# germanium_diode_radio.net
KiCad netlist of a schematic drawn in EAGLE
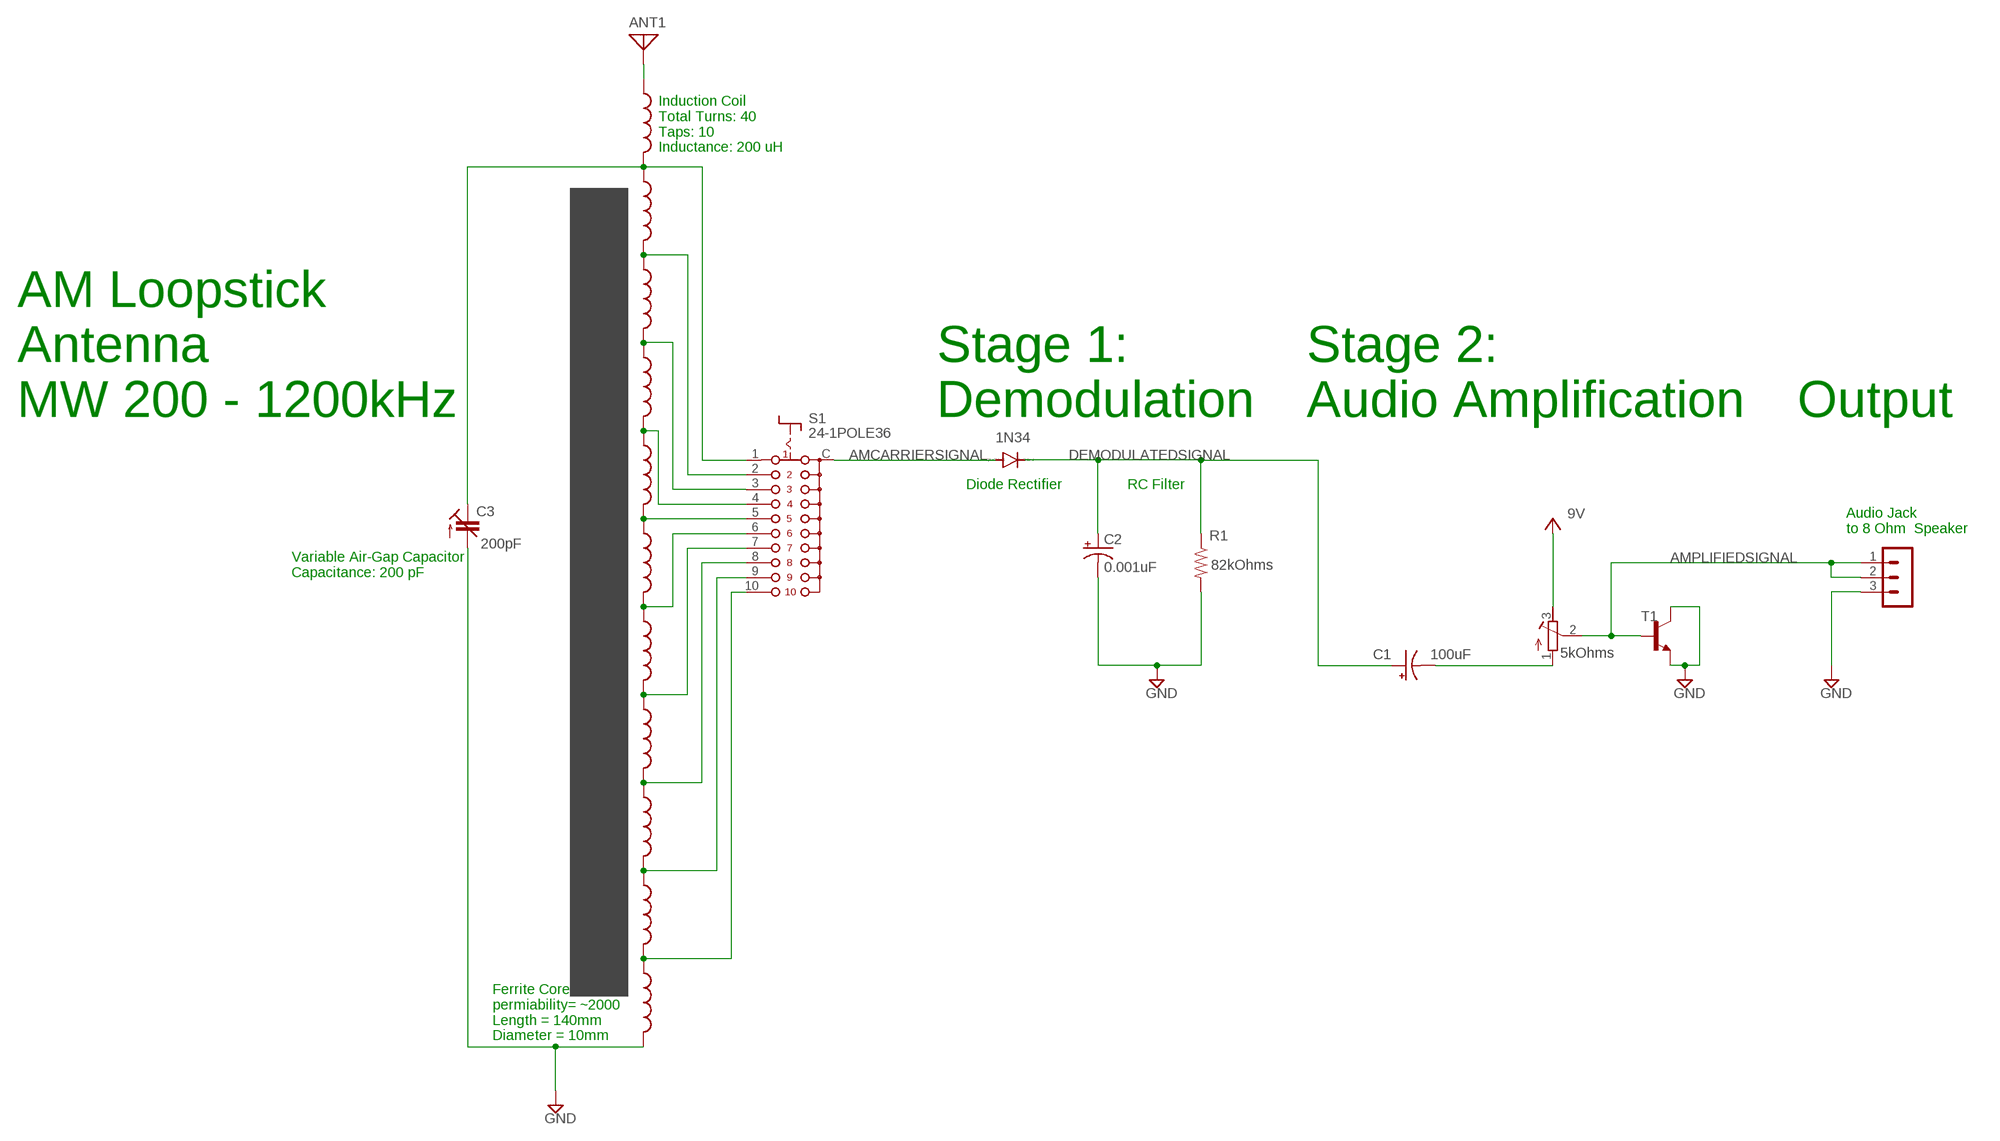
[diagram p0: schematic, sheet 1]

(export (version "E")
  (design (tool "Eeschema 10.0.6"))
  (components
    (comp (ref "1N34")
      (value "AA112")
      (footprint "eagle-import:DO07")
      (libsource (lib "eagle-import") (part "AA112"))
    )
    (comp (ref "ANT1")
      (value "ANTENNA")
      (footprint "eagle-import:PAD-01")
      (libsource (lib "eagle-import") (part "ANTENNA"))
    )
    (comp (ref "C1")
      (value "100uF")
      (footprint "eagle-import:E1,8-4")
      (libsource (lib "eagle-import") (part "CPOL-USE1.8-4"))
    )
    (comp (ref "C2")
      (value "0.001uF")
      (footprint "eagle-import:E1,8-4")
      (libsource (lib "eagle-import") (part "CPOL-USE1.8-4"))
    )
    (comp (ref "C3")
      (value "200pF")
      (footprint "eagle-import:CTRIMTZ03")
      (libsource (lib "eagle-import") (part "C-TRIMMTZ03"))
    )
    (comp (ref "L1")
      (value "L-US0204/7")
      (footprint "eagle-import:0204_7")
      (libsource (lib "eagle-import") (part "L-US0204/7"))
    )
    (comp (ref "L2")
      (value "L-US0204/7")
      (footprint "eagle-import:0204_7")
      (libsource (lib "eagle-import") (part "L-US0204/7"))
    )
    (comp (ref "L3")
      (value "L-US0204/7")
      (footprint "eagle-import:0204_7")
      (libsource (lib "eagle-import") (part "L-US0204/7"))
    )
    (comp (ref "L4")
      (value "L-US0204/7")
      (footprint "eagle-import:0204_7")
      (libsource (lib "eagle-import") (part "L-US0204/7"))
    )
    (comp (ref "L5")
      (value "L-US0204/7")
      (footprint "eagle-import:0204_7")
      (libsource (lib "eagle-import") (part "L-US0204/7"))
    )
    (comp (ref "L6")
      (value "L-US0204/7")
      (footprint "eagle-import:0204_7")
      (libsource (lib "eagle-import") (part "L-US0204/7"))
    )
    (comp (ref "L7")
      (value "L-US0204/7")
      (footprint "eagle-import:0204_7")
      (libsource (lib "eagle-import") (part "L-US0204/7"))
    )
    (comp (ref "L8")
      (value "L-US0204/7")
      (footprint "eagle-import:0204_7")
      (libsource (lib "eagle-import") (part "L-US0204/7"))
    )
    (comp (ref "L9")
      (value "L-US0204/7")
      (footprint "eagle-import:0204_7")
      (libsource (lib "eagle-import") (part "L-US0204/7"))
    )
    (comp (ref "L10")
      (value "L-US0204/7")
      (footprint "eagle-import:0204_7")
      (libsource (lib "eagle-import") (part "L-US0204/7"))
    )
    (comp (ref "L11")
      (value "L-US0204/7")
      (footprint "eagle-import:0204_7")
      (libsource (lib "eagle-import") (part "L-US0204/7"))
    )
    (comp (ref "R1")
      (value "82kOhms")
      (footprint "eagle-import:0204_7")
      (libsource (lib "eagle-import") (part "R-US_0204/7"))
    )
    (comp (ref "R2")
      (value "5kOhms")
      (footprint "eagle-import:RTRIM3296W")
      (libsource (lib "eagle-import") (part "R-TRIMM3296W"))
    )
    (comp (ref "S1")
      (value "24-1POLE36")
      (footprint "eagle-import:24-1POLE36")
      (libsource (lib "eagle-import") (part "24-1POLE36"))
    )
    (comp (ref "SV1")
      (value "MA03-1")
      (footprint "eagle-import:MA03-1")
      (libsource (lib "eagle-import") (part "MA03-1"))
    )
    (comp (ref "T1")
      (value "MPS2222A-NPN-TO92-CBE")
      (footprint "eagle-import:TO92-CBE")
      (libsource (lib "eagle-import") (part "-NPN-TO92-CBEMPS2222A"))
    )
  )
  (nets
    (net (code "1") (name "/AMCARRIERSIGNAL") (class "Default")
      (node (ref "1N34") (pin "A") (pinfunction "A_A") (pintype "passive"))
      (node (ref "S1") (pin "C") (pinfunction "S_C") (pintype "passive"))
    )
    (net (code "2") (name "/AMPLIFIEDSIGNAL") (class "Default")
      (node (ref "R2") (pin "2") (pinfunction "S_2") (pintype "passive"))
      (node (ref "SV1") (pin "1") (pinfunction "1_1") (pintype "passive"))
      (node (ref "SV1") (pin "2") (pinfunction "2_2") (pintype "passive"))
      (node (ref "T1") (pin "B") (pinfunction "B_B") (pintype "passive"))
    )
    (net (code "3") (name "/DEMODULATEDSIGNAL") (class "Default")
      (node (ref "1N34") (pin "C") (pinfunction "C_C") (pintype "passive"))
      (node (ref "C1") (pin "+") (pinfunction "+_+") (pintype "passive"))
      (node (ref "C2") (pin "+") (pinfunction "+_+") (pintype "passive"))
      (node (ref "R1") (pin "1") (pinfunction "1_1") (pintype "passive"))
    )
    (net (code "4") (name "9V") (class "Default")
      (node (ref "R2") (pin "3") (pinfunction "E_3") (pintype "passive"))
    )
    (net (code "5") (name "GND") (class "Default")
      (node (ref "C2") (pin "-") (pinfunction "-_-") (pintype "passive"))
      (node (ref "C3") (pin "2") (pinfunction "A_2") (pintype "passive"))
      (node (ref "L11") (pin "2") (pinfunction "2_2") (pintype "passive"))
      (node (ref "R1") (pin "2") (pinfunction "2_2") (pintype "passive"))
      (node (ref "SV1") (pin "3") (pinfunction "3_3") (pintype "passive"))
      (node (ref "T1") (pin "C") (pinfunction "C_C") (pintype "passive"))
      (node (ref "T1") (pin "E") (pinfunction "E_E") (pintype "passive"))
    )
    (net (code "6") (name "Net-(ANT1-Pad1)") (class "Default")
      (node (ref "ANT1") (pin "1") (pinfunction "1_1") (pintype "output"))
      (node (ref "L10") (pin "1") (pinfunction "1_1") (pintype "passive"))
    )
    (net (code "7") (name "Net-(C3-E)") (class "Default")
      (node (ref "C3") (pin "1") (pinfunction "E_1") (pintype "passive"))
      (node (ref "L10") (pin "2") (pinfunction "2_2") (pintype "passive"))
      (node (ref "L4") (pin "1") (pinfunction "1_1") (pintype "passive"))
      (node (ref "S1") (pin "1") (pinfunction "1_1") (pintype "passive"))
    )
    (net (code "8") (name "Net-(L1-Pad1)") (class "Default")
      (node (ref "L1") (pin "1") (pinfunction "1_1") (pintype "passive"))
      (node (ref "L3") (pin "2") (pinfunction "2_2") (pintype "passive"))
      (node (ref "S1") (pin "3") (pinfunction "3_3") (pintype "passive"))
    )
    (net (code "9") (name "Net-(L1-Pad2)") (class "Default")
      (node (ref "L1") (pin "2") (pinfunction "2_2") (pintype "passive"))
      (node (ref "L2") (pin "1") (pinfunction "1_1") (pintype "passive"))
      (node (ref "S1") (pin "4") (pinfunction "4_4") (pintype "passive"))
    )
    (net (code "10") (name "Net-(L2-Pad2)") (class "Default")
      (node (ref "L2") (pin "2") (pinfunction "2_2") (pintype "passive"))
      (node (ref "L5") (pin "1") (pinfunction "1_1") (pintype "passive"))
      (node (ref "S1") (pin "5") (pinfunction "5_5") (pintype "passive"))
    )
    (net (code "11") (name "Net-(L3-Pad1)") (class "Default")
      (node (ref "L3") (pin "1") (pinfunction "1_1") (pintype "passive"))
      (node (ref "L4") (pin "2") (pinfunction "2_2") (pintype "passive"))
      (node (ref "S1") (pin "2") (pinfunction "2_2") (pintype "passive"))
    )
    (net (code "12") (name "Net-(L5-Pad2)") (class "Default")
      (node (ref "L5") (pin "2") (pinfunction "2_2") (pintype "passive"))
      (node (ref "L6") (pin "1") (pinfunction "1_1") (pintype "passive"))
      (node (ref "S1") (pin "6") (pinfunction "6_6") (pintype "passive"))
    )
    (net (code "13") (name "Net-(L6-Pad2)") (class "Default")
      (node (ref "L6") (pin "2") (pinfunction "2_2") (pintype "passive"))
      (node (ref "L7") (pin "1") (pinfunction "1_1") (pintype "passive"))
      (node (ref "S1") (pin "7") (pinfunction "7_7") (pintype "passive"))
    )
    (net (code "14") (name "Net-(L7-Pad2)") (class "Default")
      (node (ref "L7") (pin "2") (pinfunction "2_2") (pintype "passive"))
      (node (ref "L8") (pin "1") (pinfunction "1_1") (pintype "passive"))
      (node (ref "S1") (pin "8") (pinfunction "8_8") (pintype "passive"))
    )
    (net (code "15") (name "Net-(L8-Pad2)") (class "Default")
      (node (ref "L8") (pin "2") (pinfunction "2_2") (pintype "passive"))
      (node (ref "L9") (pin "1") (pinfunction "1_1") (pintype "passive"))
      (node (ref "S1") (pin "9") (pinfunction "9_9") (pintype "passive"))
    )
    (net (code "16") (name "Net-(L11-Pad1)") (class "Default")
      (node (ref "L11") (pin "1") (pinfunction "1_1") (pintype "passive"))
      (node (ref "L9") (pin "2") (pinfunction "2_2") (pintype "passive"))
      (node (ref "S1") (pin "10") (pinfunction "10_10") (pintype "passive"))
    )
    (net (code "17") (name "Net-(R2-A)") (class "Default")
      (node (ref "C1") (pin "-") (pinfunction "-_-") (pintype "passive"))
      (node (ref "R2") (pin "1") (pinfunction "A_1") (pintype "passive"))
    )
  )
)
